# DB_Bypass.net
KiCad netlist of a schematic drawn in Altium Designer
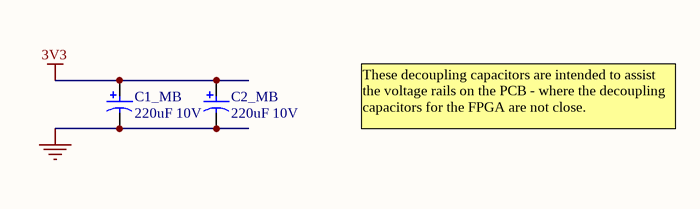
[diagram p0: DB_Bypass.SchDoc]

(export (version "E")
  (design (tool "Eeschema 10.0.6"))
  (components
    (comp (ref "C1_MB")
      (value "220uF 10V")
      (footprint "CAPC7343-STAR")
      (description "Capacitor, Tantalum, 220uF 10% 10V MCCT-D (7343-31)")
      (fields (field (name "TOLERANCE") "10 %"))
      (libsource (lib "AltiumDesignLibrary") (part "CAP-P"))
    )
    (comp (ref "C2_MB")
      (value "220uF 10V")
      (footprint "CAPC7343-STAR")
      (description "Capacitor, Tantalum, 220uF 10% 10V MCCT-D (7343-31)")
      (fields (field (name "TOLERANCE") "10 %"))
      (libsource (lib "AltiumDesignLibrary") (part "CAP-P"))
    )
  )
  (nets
    (net (code "1") (name "3V3") (class "Default")
      (node (ref "C1_MB") (pin "1") (pinfunction "1_1") (pintype "passive"))
      (node (ref "C2_MB") (pin "1") (pinfunction "1_1") (pintype "passive"))
    )
    (net (code "2") (name "GND") (class "Default")
      (node (ref "C1_MB") (pin "2") (pinfunction "2_2") (pintype "passive"))
      (node (ref "C2_MB") (pin "2") (pinfunction "2_2") (pintype "passive"))
    )
  )
)
